# femto-beacon-esp32pico-d4-coin.net
KiCad netlist of a schematic drawn in EAGLE
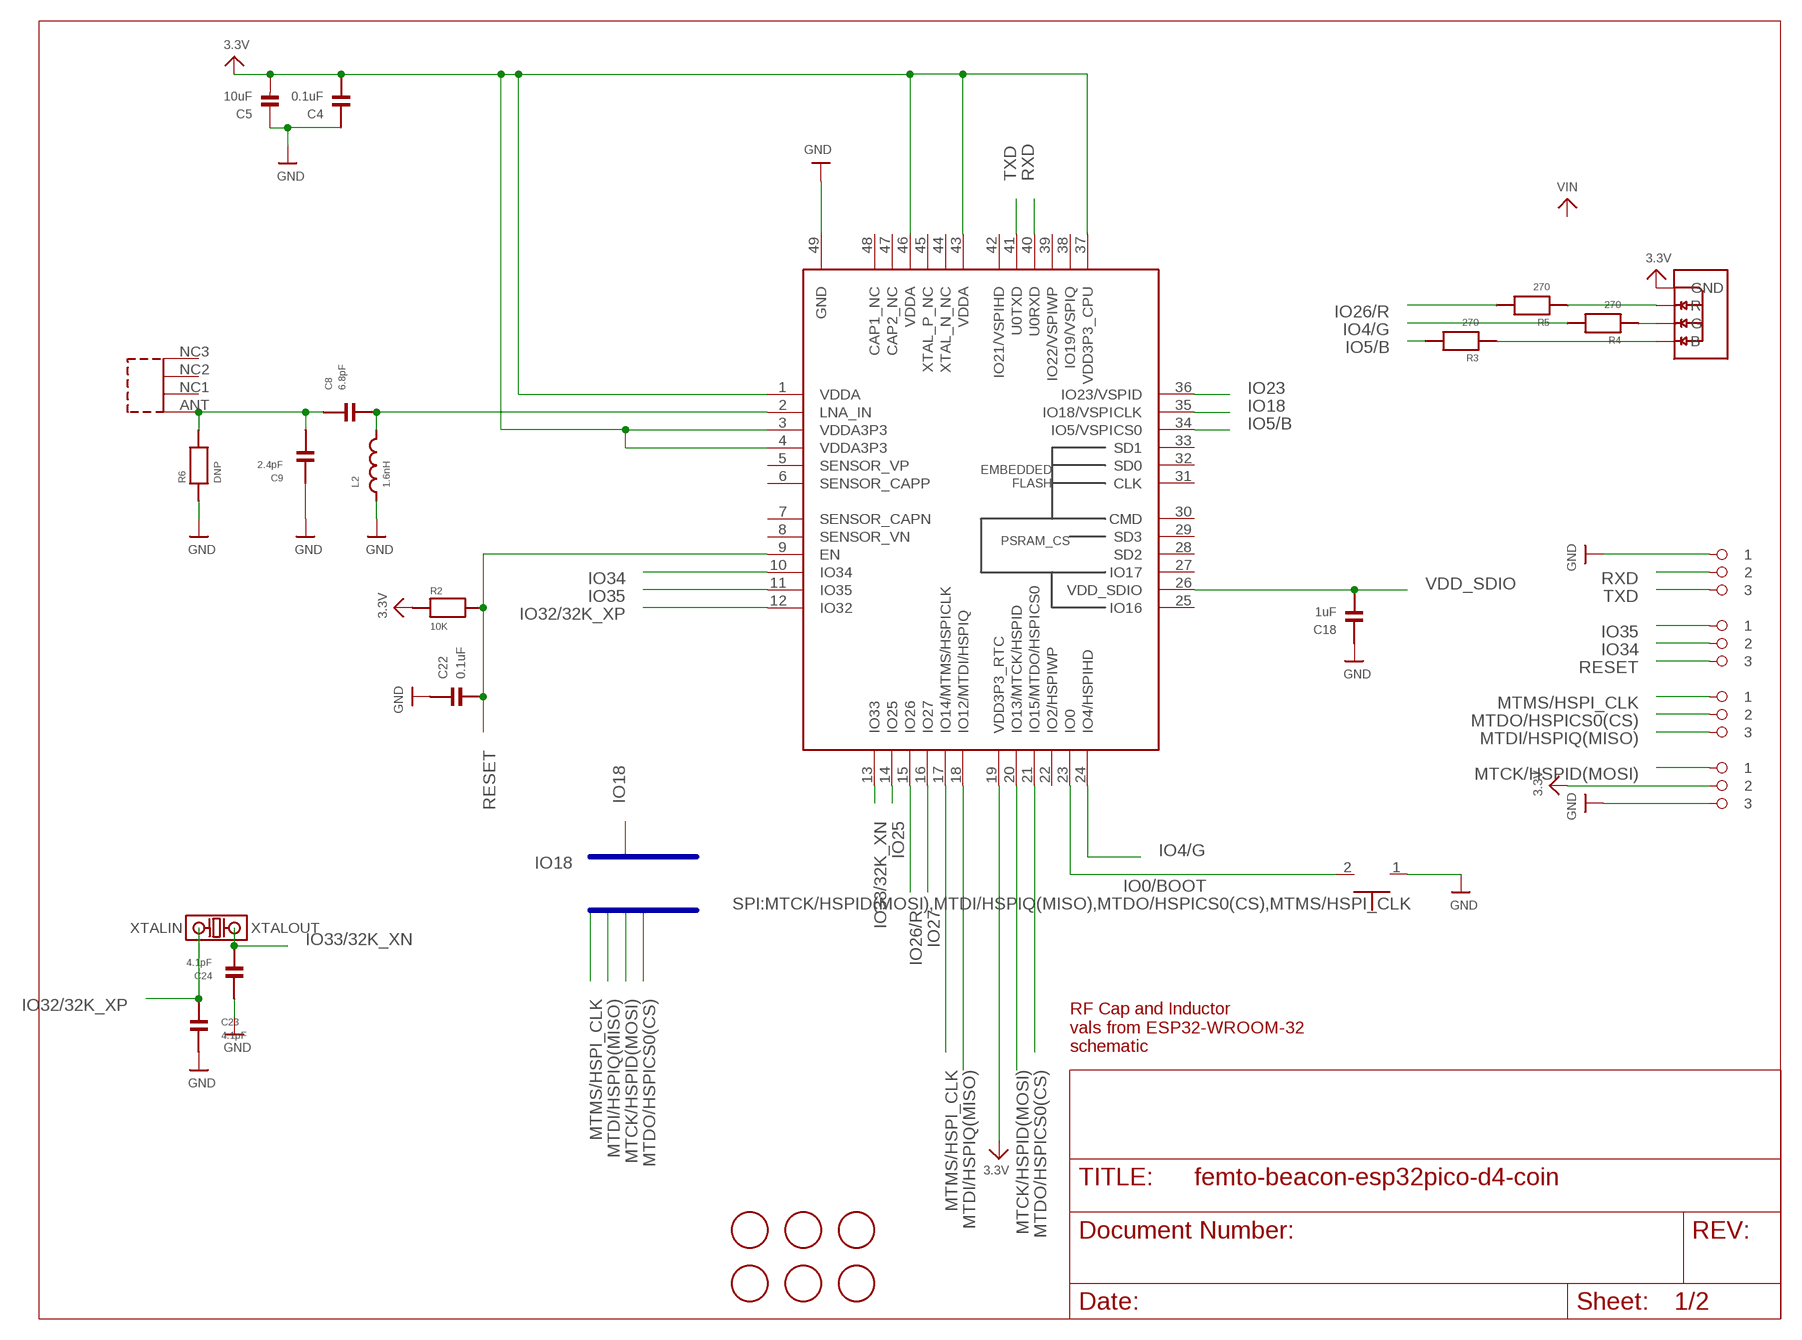
[diagram p0: schematic, sheet 1]
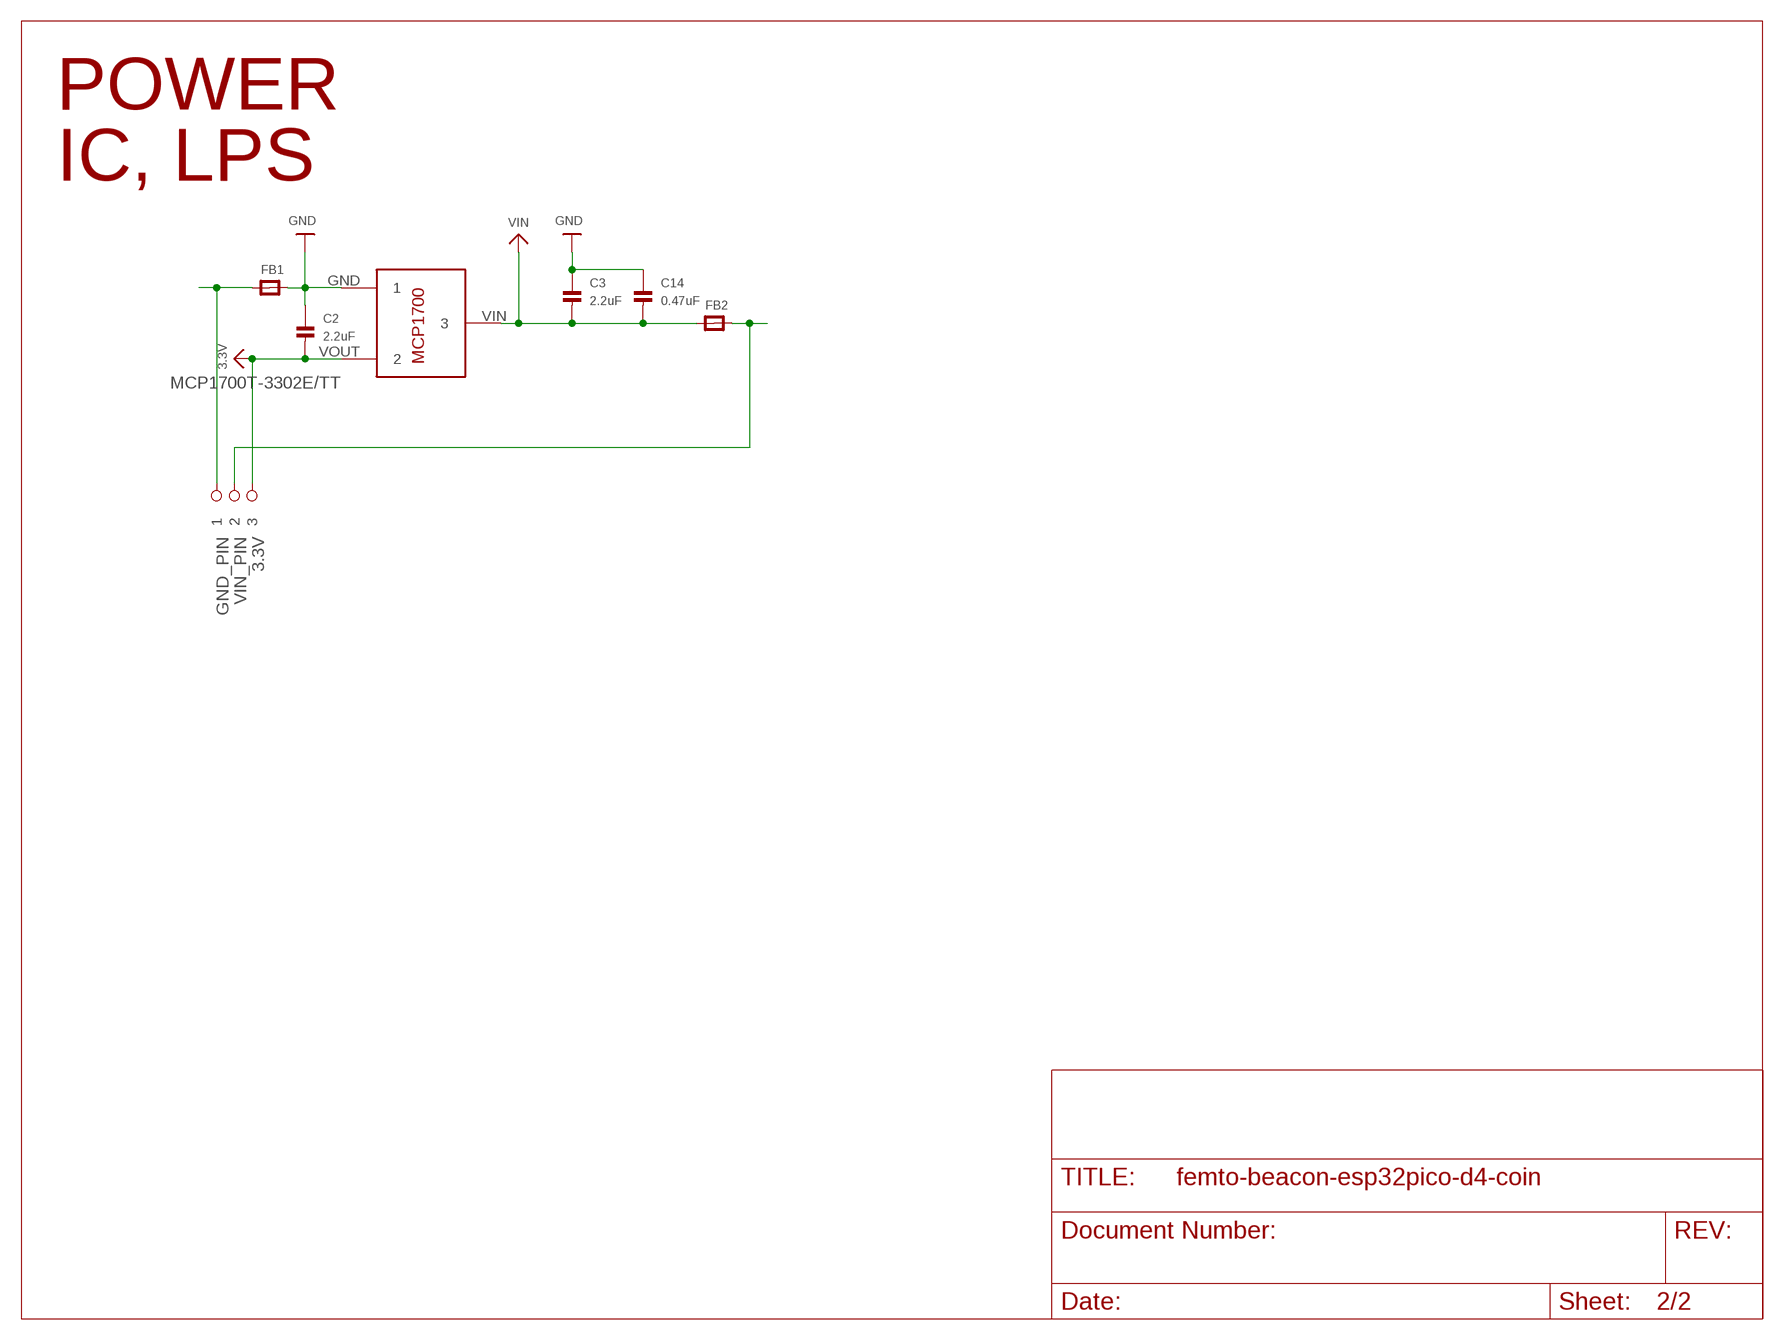
[diagram p1: schematic, sheet 2]

(export (version "E")
  (design (tool "Eeschema 10.0.6"))
  (components
    (comp (ref "ANT1")
      (value "0479480001")
      (footprint "eagle-import:0479480001")
      (libsource (lib "eagle-import") (part "0479480001"))
    )
    (comp (ref "BOOT1")
      (value "TACTILE_SWITCH_NO_GND_NO_BOSS")
      (footprint "eagle-import:SIDE_ACT_NO_GND_NO_BOSS")
      (fields (field (name "MPN") "B3U-3000P"))
      (libsource (lib "eagle-import") (part "TACTILE_SWITCH_NO_GND_NO_BOSS"))
    )
    (comp (ref "C4")
      (value "0.1uF")
      (footprint "eagle-import:PART")
      (fields (field (name "MPN") "GRM033C80J104KE84D"))
      (libsource (lib "eagle-import") (part "CAPACITOR_0201"))
    )
    (comp (ref "C5")
      (value "10uF")
      (footprint "eagle-import:_0603MP")
      (fields (field (name "MPN") "GRM188R61C106KAALD"))
      (libsource (lib "eagle-import") (part "CAP_CERAMIC_0603MP"))
    )
    (comp (ref "C8")
      (value "6.8pF")
      (footprint "eagle-import:PART")
      (fields (field (name "MPN") "GRM0335C2A6R8DA01D"))
      (libsource (lib "eagle-import") (part "CAPACITOR_0201"))
    )
    (comp (ref "C9")
      (value "2.4pF")
      (footprint "eagle-import:PART")
      (fields (field (name "MPN") "GRM0335C1H2R4CA01D"))
      (libsource (lib "eagle-import") (part "CAPACITOR_0201"))
    )
    (comp (ref "C18")
      (value "1uF")
      (footprint "eagle-import:PART")
      (fields (field (name "MPN") "CL03A105KQ3CSNH"))
      (libsource (lib "eagle-import") (part "CAPACITOR_0201"))
    )
    (comp (ref "C22")
      (value "0.1uF")
      (footprint "eagle-import:PART")
      (fields (field (name "MPN") "GRM033C80J104KE84D"))
      (libsource (lib "eagle-import") (part "CAPACITOR_0201"))
    )
    (comp (ref "C23")
      (value "4.1pF")
      (footprint "eagle-import:PART")
      (fields (field (name "MPN") "GRM0335C1H4R1BA01D"))
      (libsource (lib "eagle-import") (part "CAPACITOR_0201"))
    )
    (comp (ref "C24")
      (value "4.1pF")
      (footprint "eagle-import:PART")
      (fields (field (name "MPN") "GRM0335C1H4R1BA01D"))
      (libsource (lib "eagle-import") (part "CAPACITOR_0201"))
    )
    (comp (ref "FID1")
      (value "FIDUCIAL")
      (footprint "eagle-import:FIDUCIAL_1MM")
      (libsource (lib "eagle-import") (part "FIDUCIAL"))
    )
    (comp (ref "FID2")
      (value "FIDUCIAL")
      (footprint "eagle-import:FIDUCIAL_1MM")
      (libsource (lib "eagle-import") (part "FIDUCIAL"))
    )
    (comp (ref "FID3")
      (value "FIDUCIAL")
      (footprint "eagle-import:FIDUCIAL_1MM")
      (libsource (lib "eagle-import") (part "FIDUCIAL"))
    )
    (comp (ref "FID4")
      (value "FIDUCIAL")
      (footprint "eagle-import:FIDUCIAL_1MM")
      (libsource (lib "eagle-import") (part "FIDUCIAL"))
    )
    (comp (ref "FID5")
      (value "FIDUCIAL")
      (footprint "eagle-import:FIDUCIAL_1MM")
      (libsource (lib "eagle-import") (part "FIDUCIAL"))
    )
    (comp (ref "FID6")
      (value "FIDUCIAL")
      (footprint "eagle-import:FIDUCIAL_1MM")
      (libsource (lib "eagle-import") (part "FIDUCIAL"))
    )
    (comp (ref "IC1")
      (value "ESP32-PICO-D4")
      (footprint "eagle-import:ESP32-QFN48_7X7")
      (libsource (lib "eagle-import") (part "ESP32-PICO-D4"))
    )
    (comp (ref "L2")
      (value "1.6nH")
      (footprint "eagle-import:PART")
      (fields (field (name "MPN") "LQP03HQ1N6B02D"))
      (libsource (lib "eagle-import") (part "INDUCTOR_FIXED_0201"))
    )
    (comp (ref "PIN_EN")
      (value "1X3_ROUND")
      (footprint "eagle-import:1X3_ROUND")
      (libsource (lib "eagle-import") (part "1X3_ROUND"))
    )
    (comp (ref "PIN_GPIO_A")
      (value "1X3_ROUND")
      (footprint "eagle-import:1X3_ROUND")
      (libsource (lib "eagle-import") (part "1X3_ROUND"))
    )
    (comp (ref "PIN_GPIO_B")
      (value "1X3_ROUND")
      (footprint "eagle-import:1X3_ROUND")
      (libsource (lib "eagle-import") (part "1X3_ROUND"))
    )
    (comp (ref "PIN_UART")
      (value "1X3_ROUND")
      (footprint "eagle-import:1X3_ROUND")
      (libsource (lib "eagle-import") (part "1X3_ROUND"))
    )
    (comp (ref "R2")
      (value "10K")
      (footprint "eagle-import:PART")
      (fields (field (name "MPN") "RC0201JR-0710KL"))
      (libsource (lib "eagle-import") (part "RESISTOR_0201"))
    )
    (comp (ref "R3")
      (value "270")
      (footprint "eagle-import:PART")
      (fields (field (name "MPN") "RC0201FR-07270RL"))
      (libsource (lib "eagle-import") (part "RESISTOR_0201"))
    )
    (comp (ref "R4")
      (value "270")
      (footprint "eagle-import:PART")
      (fields (field (name "MPN") "RC0201FR-07270RL"))
      (libsource (lib "eagle-import") (part "RESISTOR_0201"))
    )
    (comp (ref "R5")
      (value "270")
      (footprint "eagle-import:PART")
      (fields (field (name "MPN") "RC0201FR-07270RL"))
      (libsource (lib "eagle-import") (part "RESISTOR_0201"))
    )
    (comp (ref "R6")
      (value "DNP")
      (footprint "eagle-import:PART")
      (libsource (lib "eagle-import") (part "RESISTOR_0201"))
    )
    (comp (ref "RGB1")
      (value "LRTB_R48G")
      (footprint "eagle-import:LRTB_R48G")
      (fields (field (name "MPN") "LRTB R48G"))
      (libsource (lib "eagle-import") (part "LRTB_R48G"))
    )
    (comp (ref "XTAL2")
      (value "ABS06-107-32.768KHZ-T")
      (footprint "eagle-import:ABS06-107-32.768KHZ-T")
      (fields (field (name "MPN") "ABS06-107-32.768kHz-T"))
      (libsource (lib "eagle-import") (part "ABS06-107-32.768KHZ-T"))
    )
    (comp (ref "C2")
      (value "2.2uF")
      (footprint "eagle-import:_0402MP")
      (fields (field (name "MPN") "C1005X5R0J225K050BC"))
      (libsource (lib "eagle-import") (part "CAP_CERAMIC_0402MP"))
    )
    (comp (ref "C3")
      (value "2.2uF")
      (footprint "eagle-import:_0402MP")
      (fields (field (name "MPN") "C1005X5R0J225K050BC"))
      (libsource (lib "eagle-import") (part "CAP_CERAMIC_0402MP"))
    )
    (comp (ref "C14")
      (value "0.47uF")
      (footprint "eagle-import:_0402MP")
      (fields (field (name "MPN") "GRM155R60J474KE19D"))
      (libsource (lib "eagle-import") (part "CAP_CERAMIC_0402MP"))
    )
    (comp (ref "FB1")
      (value "FERRITE_0603MP")
      (footprint "eagle-import:_0603MP")
      (fields (field (name "MPN") "BLM18RK102SN1D"))
      (libsource (lib "eagle-import") (part "FERRITE_0603MP"))
    )
    (comp (ref "FB2")
      (value "FERRITE_0603MP")
      (footprint "eagle-import:_0603MP")
      (fields (field (name "MPN") "BLM18RK102SN1D"))
      (libsource (lib "eagle-import") (part "FERRITE_0603MP"))
    )
    (comp (ref "LDO1")
      (value "MCP1700T-3302E/TT")
      (footprint "eagle-import:MCP1700T-3302E_TT")
      (libsource (lib "eagle-import") (part "MCP1700T-3302E/TT"))
    )
    (comp (ref "PIN_PWR")
      (value "1X3_ROUND")
      (footprint "eagle-import:1X3_ROUND")
      (libsource (lib "eagle-import") (part "1X3_ROUND"))
    )
  )
  (nets
    (net (code "4") (name "3.3V") (class "Default")
      (node (ref "C2") (pin "2") (pinfunction "P$2_2") (pintype "passive"))
      (node (ref "C4") (pin "2") (pinfunction "P$2_2") (pintype "bidirectional"))
      (node (ref "C5") (pin "2") (pinfunction "P$2_2") (pintype "passive"))
      (node (ref "IC1") (pin "1") (pinfunction "VDDA_1") (pintype "power_in"))
      (node (ref "IC1") (pin "19") (pinfunction "VDD3P3_RTC_19") (pintype "power_in"))
      (node (ref "IC1") (pin "3") (pinfunction "VDDA3P3_3") (pintype "power_in"))
      (node (ref "IC1") (pin "37") (pinfunction "VDD3P3_CPU_37") (pintype "power_in"))
      (node (ref "IC1") (pin "4") (pinfunction "VDDA3P3_4") (pintype "power_in"))
      (node (ref "IC1") (pin "43") (pinfunction "VDDA_43") (pintype "power_in"))
      (node (ref "IC1") (pin "46") (pinfunction "VDDA_46") (pintype "power_in"))
      (node (ref "LDO1") (pin "VOUT") (pinfunction "2_VOUT") (pintype "bidirectional"))
      (node (ref "PIN_GPIO_A") (pin "P$2") (pinfunction "2_P$2") (pintype "bidirectional"))
      (node (ref "PIN_PWR") (pin "P$3") (pinfunction "3_P$3") (pintype "bidirectional"))
      (node (ref "R2") (pin "1") (pinfunction "1_1") (pintype "bidirectional"))
      (node (ref "RGB1") (pin "1") (pinfunction "GND_1") (pintype "bidirectional"))
    )
    (net (code "5") (name "GND") (class "Default")
      (node (ref "BOOT1") (pin "1") (pinfunction "1_1") (pintype "bidirectional"))
      (node (ref "C14") (pin "1") (pinfunction "P$1_1") (pintype "passive"))
      (node (ref "C18") (pin "1") (pinfunction "P$1_1") (pintype "bidirectional"))
      (node (ref "C2") (pin "1") (pinfunction "P$1_1") (pintype "passive"))
      (node (ref "C22") (pin "1") (pinfunction "P$1_1") (pintype "bidirectional"))
      (node (ref "C23") (pin "1") (pinfunction "P$1_1") (pintype "bidirectional"))
      (node (ref "C24") (pin "2") (pinfunction "P$2_2") (pintype "bidirectional"))
      (node (ref "C3") (pin "1") (pinfunction "P$1_1") (pintype "passive"))
      (node (ref "C4") (pin "1") (pinfunction "P$1_1") (pintype "bidirectional"))
      (node (ref "C5") (pin "1") (pinfunction "P$1_1") (pintype "passive"))
      (node (ref "C9") (pin "1") (pinfunction "P$1_1") (pintype "bidirectional"))
      (node (ref "FB1") (pin "2") (pinfunction "P$2_2") (pintype "passive"))
      (node (ref "IC1") (pin "49") (pinfunction "GND_49") (pintype "bidirectional"))
      (node (ref "L2") (pin "1") (pinfunction "P$1_1") (pintype "bidirectional"))
      (node (ref "LDO1") (pin "GND") (pinfunction "1_GND") (pintype "bidirectional"))
      (node (ref "PIN_GPIO_A") (pin "P$3") (pinfunction "3_P$3") (pintype "bidirectional"))
      (node (ref "PIN_UART") (pin "P$1") (pinfunction "1_P$1") (pintype "bidirectional"))
      (node (ref "R6") (pin "1") (pinfunction "1_1") (pintype "bidirectional"))
    )
    (net (code "6") (name "GND_PIN") (class "Default")
      (node (ref "FB1") (pin "1") (pinfunction "P$1_1") (pintype "passive"))
      (node (ref "PIN_PWR") (pin "P$1") (pinfunction "1_P$1") (pintype "bidirectional"))
    )
    (net (code "7") (name "IO0{slash}BOOT") (class "Default")
      (node (ref "BOOT1") (pin "2") (pinfunction "2_2") (pintype "bidirectional"))
      (node (ref "IC1") (pin "23") (pinfunction "IO0_23") (pintype "bidirectional"))
    )
    (net (code "8") (name "IO4{slash}G") (class "Default")
      (node (ref "IC1") (pin "24") (pinfunction "IO4/HSPIHD_24") (pintype "bidirectional"))
      (node (ref "R4") (pin "2") (pinfunction "2_2") (pintype "bidirectional"))
    )
    (net (code "9") (name "IO5{slash}B") (class "Default")
      (node (ref "IC1") (pin "34") (pinfunction "IO5/VSPICS0_34") (pintype "bidirectional"))
      (node (ref "R3") (pin "2") (pinfunction "2_2") (pintype "bidirectional"))
    )
    (net (code "10") (name "IO18") (class "Default")
      (node (ref "IC1") (pin "35") (pinfunction "IO18/VSPICLK_35") (pintype "bidirectional"))
    )
    (net (code "11") (name "IO23") (class "Default")
      (node (ref "IC1") (pin "36") (pinfunction "IO23/VSPID_36") (pintype "bidirectional"))
    )
    (net (code "12") (name "IO25") (class "Default")
      (node (ref "IC1") (pin "14") (pinfunction "IO25_14") (pintype "bidirectional"))
    )
    (net (code "13") (name "IO26{slash}R") (class "Default")
      (node (ref "IC1") (pin "15") (pinfunction "IO26_15") (pintype "bidirectional"))
      (node (ref "R5") (pin "2") (pinfunction "2_2") (pintype "bidirectional"))
    )
    (net (code "14") (name "IO27") (class "Default")
      (node (ref "IC1") (pin "16") (pinfunction "IO27_16") (pintype "bidirectional"))
    )
    (net (code "15") (name "IO32{slash}32K_XP") (class "Default")
      (node (ref "C23") (pin "2") (pinfunction "P$2_2") (pintype "bidirectional"))
      (node (ref "IC1") (pin "12") (pinfunction "IO32_12") (pintype "bidirectional"))
      (node (ref "XTAL2") (pin "1") (pinfunction "XTALIN_1") (pintype "bidirectional"))
    )
    (net (code "16") (name "IO33{slash}32K_XN") (class "Default")
      (node (ref "C24") (pin "1") (pinfunction "P$1_1") (pintype "bidirectional"))
      (node (ref "IC1") (pin "13") (pinfunction "IO33_13") (pintype "bidirectional"))
      (node (ref "XTAL2") (pin "2") (pinfunction "XTALOUT_2") (pintype "bidirectional"))
    )
    (net (code "17") (name "IO34") (class "Default")
      (node (ref "IC1") (pin "10") (pinfunction "IO34_10") (pintype "input"))
      (node (ref "PIN_EN") (pin "P$2") (pinfunction "2_P$2") (pintype "bidirectional"))
    )
    (net (code "18") (name "IO35") (class "Default")
      (node (ref "IC1") (pin "11") (pinfunction "IO35_11") (pintype "input"))
      (node (ref "PIN_EN") (pin "P$1") (pinfunction "1_P$1") (pintype "bidirectional"))
    )
    (net (code "19") (name "MTCK{slash}HSPID(MOSI)") (class "Default")
      (node (ref "IC1") (pin "20") (pinfunction "IO13/MTCK/HSPID_20") (pintype "bidirectional"))
      (node (ref "PIN_GPIO_A") (pin "P$1") (pinfunction "1_P$1") (pintype "bidirectional"))
    )
    (net (code "20") (name "MTDI{slash}HSPIQ(MISO)") (class "Default")
      (node (ref "IC1") (pin "18") (pinfunction "IO12/MTDI/HSPIQ_18") (pintype "bidirectional"))
      (node (ref "PIN_GPIO_B") (pin "P$3") (pinfunction "3_P$3") (pintype "bidirectional"))
    )
    (net (code "21") (name "MTDO{slash}HSPICS0(CS)") (class "Default")
      (node (ref "IC1") (pin "21") (pinfunction "IO15/MTDO/HSPICS0_21") (pintype "bidirectional"))
      (node (ref "PIN_GPIO_B") (pin "P$2") (pinfunction "2_P$2") (pintype "bidirectional"))
    )
    (net (code "22") (name "MTMS{slash}HSPI_CLK") (class "Default")
      (node (ref "IC1") (pin "17") (pinfunction "IO14/MTMS/HSPICLK_17") (pintype "bidirectional"))
      (node (ref "PIN_GPIO_B") (pin "P$1") (pinfunction "1_P$1") (pintype "bidirectional"))
    )
    (net (code "23") (name "Net-(ANT1-1)") (class "Default")
      (node (ref "ANT1") (pin "ANT") (pinfunction "1_ANT") (pintype "bidirectional"))
      (node (ref "C8") (pin "1") (pinfunction "P$1_1") (pintype "bidirectional"))
      (node (ref "C9") (pin "2") (pinfunction "P$2_2") (pintype "bidirectional"))
      (node (ref "R6") (pin "2") (pinfunction "2_2") (pintype "bidirectional"))
    )
    (net (code "24") (name "Net-(C8-P$2)") (class "Default")
      (node (ref "C8") (pin "2") (pinfunction "P$2_2") (pintype "bidirectional"))
      (node (ref "IC1") (pin "2") (pinfunction "LNA_IN_2") (pintype "bidirectional"))
      (node (ref "L2") (pin "2") (pinfunction "P$2_2") (pintype "bidirectional"))
    )
    (net (code "25") (name "Net-(RGB1-B)") (class "Default")
      (node (ref "R3") (pin "1") (pinfunction "1_1") (pintype "bidirectional"))
      (node (ref "RGB1") (pin "4") (pinfunction "B_4") (pintype "bidirectional"))
    )
    (net (code "26") (name "Net-(RGB1-G)") (class "Default")
      (node (ref "R4") (pin "1") (pinfunction "1_1") (pintype "bidirectional"))
      (node (ref "RGB1") (pin "3") (pinfunction "G_3") (pintype "bidirectional"))
    )
    (net (code "27") (name "Net-(RGB1-R)") (class "Default")
      (node (ref "R5") (pin "1") (pinfunction "1_1") (pintype "bidirectional"))
      (node (ref "RGB1") (pin "2") (pinfunction "R_2") (pintype "bidirectional"))
    )
    (net (code "28") (name "RESET") (class "Default")
      (node (ref "C22") (pin "2") (pinfunction "P$2_2") (pintype "bidirectional"))
      (node (ref "IC1") (pin "9") (pinfunction "EN_9") (pintype "input"))
      (node (ref "PIN_EN") (pin "P$3") (pinfunction "3_P$3") (pintype "bidirectional"))
      (node (ref "R2") (pin "2") (pinfunction "2_2") (pintype "bidirectional"))
    )
    (net (code "29") (name "RXD") (class "Default")
      (node (ref "IC1") (pin "40") (pinfunction "U0RXD_40") (pintype "bidirectional"))
      (node (ref "PIN_UART") (pin "P$2") (pinfunction "2_P$2") (pintype "bidirectional"))
    )
    (net (code "30") (name "TXD") (class "Default")
      (node (ref "IC1") (pin "41") (pinfunction "U0TXD_41") (pintype "bidirectional"))
      (node (ref "PIN_UART") (pin "P$3") (pinfunction "3_P$3") (pintype "bidirectional"))
    )
    (net (code "31") (name "VDD_SDIO") (class "Default")
      (node (ref "C18") (pin "2") (pinfunction "P$2_2") (pintype "bidirectional"))
      (node (ref "IC1") (pin "26") (pinfunction "VDD_SDIO_26") (pintype "power_in"))
    )
    (net (code "32") (name "VIN") (class "Default")
      (node (ref "C14") (pin "2") (pinfunction "P$2_2") (pintype "passive"))
      (node (ref "C3") (pin "2") (pinfunction "P$2_2") (pintype "passive"))
      (node (ref "FB2") (pin "1") (pinfunction "P$1_1") (pintype "passive"))
      (node (ref "LDO1") (pin "VIN") (pinfunction "3_VIN") (pintype "bidirectional"))
    )
    (net (code "33") (name "VIN_PIN") (class "Default")
      (node (ref "FB2") (pin "2") (pinfunction "P$2_2") (pintype "passive"))
      (node (ref "PIN_PWR") (pin "P$2") (pinfunction "2_P$2") (pintype "bidirectional"))
    )
    (net (code "34") (name "unconnected-(ANT1-2-PadNC1)") (class "Default")
      (node (ref "ANT1") (pin "NC1") (pinfunction "2_NC1") (pintype "bidirectional"))
    )
    (net (code "35") (name "unconnected-(ANT1-3-PadNC2)") (class "Default")
      (node (ref "ANT1") (pin "NC2") (pinfunction "3_NC2") (pintype "bidirectional"))
    )
    (net (code "36") (name "unconnected-(ANT1-4-PadNC3)") (class "Default")
      (node (ref "ANT1") (pin "NC3") (pinfunction "4_NC3") (pintype "bidirectional"))
    )
    (net (code "37") (name "unconnected-(IC1-CAP1_NC-Pad48)") (class "Default")
      (node (ref "IC1") (pin "48") (pinfunction "CAP1_NC_48") (pintype "no_connect"))
    )
    (net (code "38") (name "unconnected-(IC1-CAP2_NC-Pad47)") (class "Default")
      (node (ref "IC1") (pin "47") (pinfunction "CAP2_NC_47") (pintype "no_connect"))
    )
    (net (code "39") (name "unconnected-(IC1-CLK-Pad31)") (class "Default")
      (node (ref "IC1") (pin "31") (pinfunction "CLK_31") (pintype "bidirectional"))
    )
    (net (code "40") (name "unconnected-(IC1-CMD-Pad30)") (class "Default")
      (node (ref "IC1") (pin "30") (pinfunction "CMD_30") (pintype "bidirectional"))
    )
    (net (code "41") (name "unconnected-(IC1-IO2{slash}HSPIWP-Pad22)") (class "Default")
      (node (ref "IC1") (pin "22") (pinfunction "IO2/HSPIWP_22") (pintype "bidirectional"))
    )
    (net (code "42") (name "unconnected-(IC1-IO16-Pad25)") (class "Default")
      (node (ref "IC1") (pin "25") (pinfunction "IO16_25") (pintype "bidirectional"))
    )
    (net (code "43") (name "unconnected-(IC1-IO17-Pad27)") (class "Default")
      (node (ref "IC1") (pin "27") (pinfunction "IO17_27") (pintype "bidirectional"))
    )
    (net (code "44") (name "unconnected-(IC1-IO19{slash}VSPIQ-Pad38)") (class "Default")
      (node (ref "IC1") (pin "38") (pinfunction "IO19/VSPIQ_38") (pintype "bidirectional"))
    )
    (net (code "45") (name "unconnected-(IC1-IO21{slash}VSPIHD-Pad42)") (class "Default")
      (node (ref "IC1") (pin "42") (pinfunction "IO21/VSPIHD_42") (pintype "bidirectional"))
    )
    (net (code "46") (name "unconnected-(IC1-IO22{slash}VSPIWP-Pad39)") (class "Default")
      (node (ref "IC1") (pin "39") (pinfunction "IO22/VSPIWP_39") (pintype "bidirectional"))
    )
    (net (code "47") (name "unconnected-(IC1-SD0-Pad32)") (class "Default")
      (node (ref "IC1") (pin "32") (pinfunction "SD0_32") (pintype "bidirectional"))
    )
    (net (code "48") (name "unconnected-(IC1-SD1-Pad33)") (class "Default")
      (node (ref "IC1") (pin "33") (pinfunction "SD1_33") (pintype "bidirectional"))
    )
    (net (code "49") (name "unconnected-(IC1-SD2-Pad28)") (class "Default")
      (node (ref "IC1") (pin "28") (pinfunction "SD2_28") (pintype "bidirectional"))
    )
    (net (code "50") (name "unconnected-(IC1-SD3-Pad29)") (class "Default")
      (node (ref "IC1") (pin "29") (pinfunction "SD3_29") (pintype "bidirectional"))
    )
    (net (code "51") (name "unconnected-(IC1-SENSOR_CAPN-Pad7)") (class "Default")
      (node (ref "IC1") (pin "7") (pinfunction "SENSOR_CAPN_7") (pintype "input"))
    )
    (net (code "52") (name "unconnected-(IC1-SENSOR_CAPP-Pad6)") (class "Default")
      (node (ref "IC1") (pin "6") (pinfunction "SENSOR_CAPP_6") (pintype "input"))
    )
    (net (code "53") (name "unconnected-(IC1-SENSOR_VN-Pad8)") (class "Default")
      (node (ref "IC1") (pin "8") (pinfunction "SENSOR_VN_8") (pintype "input"))
    )
    (net (code "54") (name "unconnected-(IC1-SENSOR_VP-Pad5)") (class "Default")
      (node (ref "IC1") (pin "5") (pinfunction "SENSOR_VP_5") (pintype "input"))
    )
    (net (code "55") (name "unconnected-(IC1-XTAL_N_NC-Pad44)") (class "Default")
      (node (ref "IC1") (pin "44") (pinfunction "XTAL_N_NC_44") (pintype "no_connect"))
    )
    (net (code "56") (name "unconnected-(IC1-XTAL_P_NC-Pad45)") (class "Default")
      (node (ref "IC1") (pin "45") (pinfunction "XTAL_P_NC_45") (pintype "no_connect"))
    )
  )
)
